# Adafruit_VL53L4CD.net
KiCad netlist of a schematic drawn in EAGLE
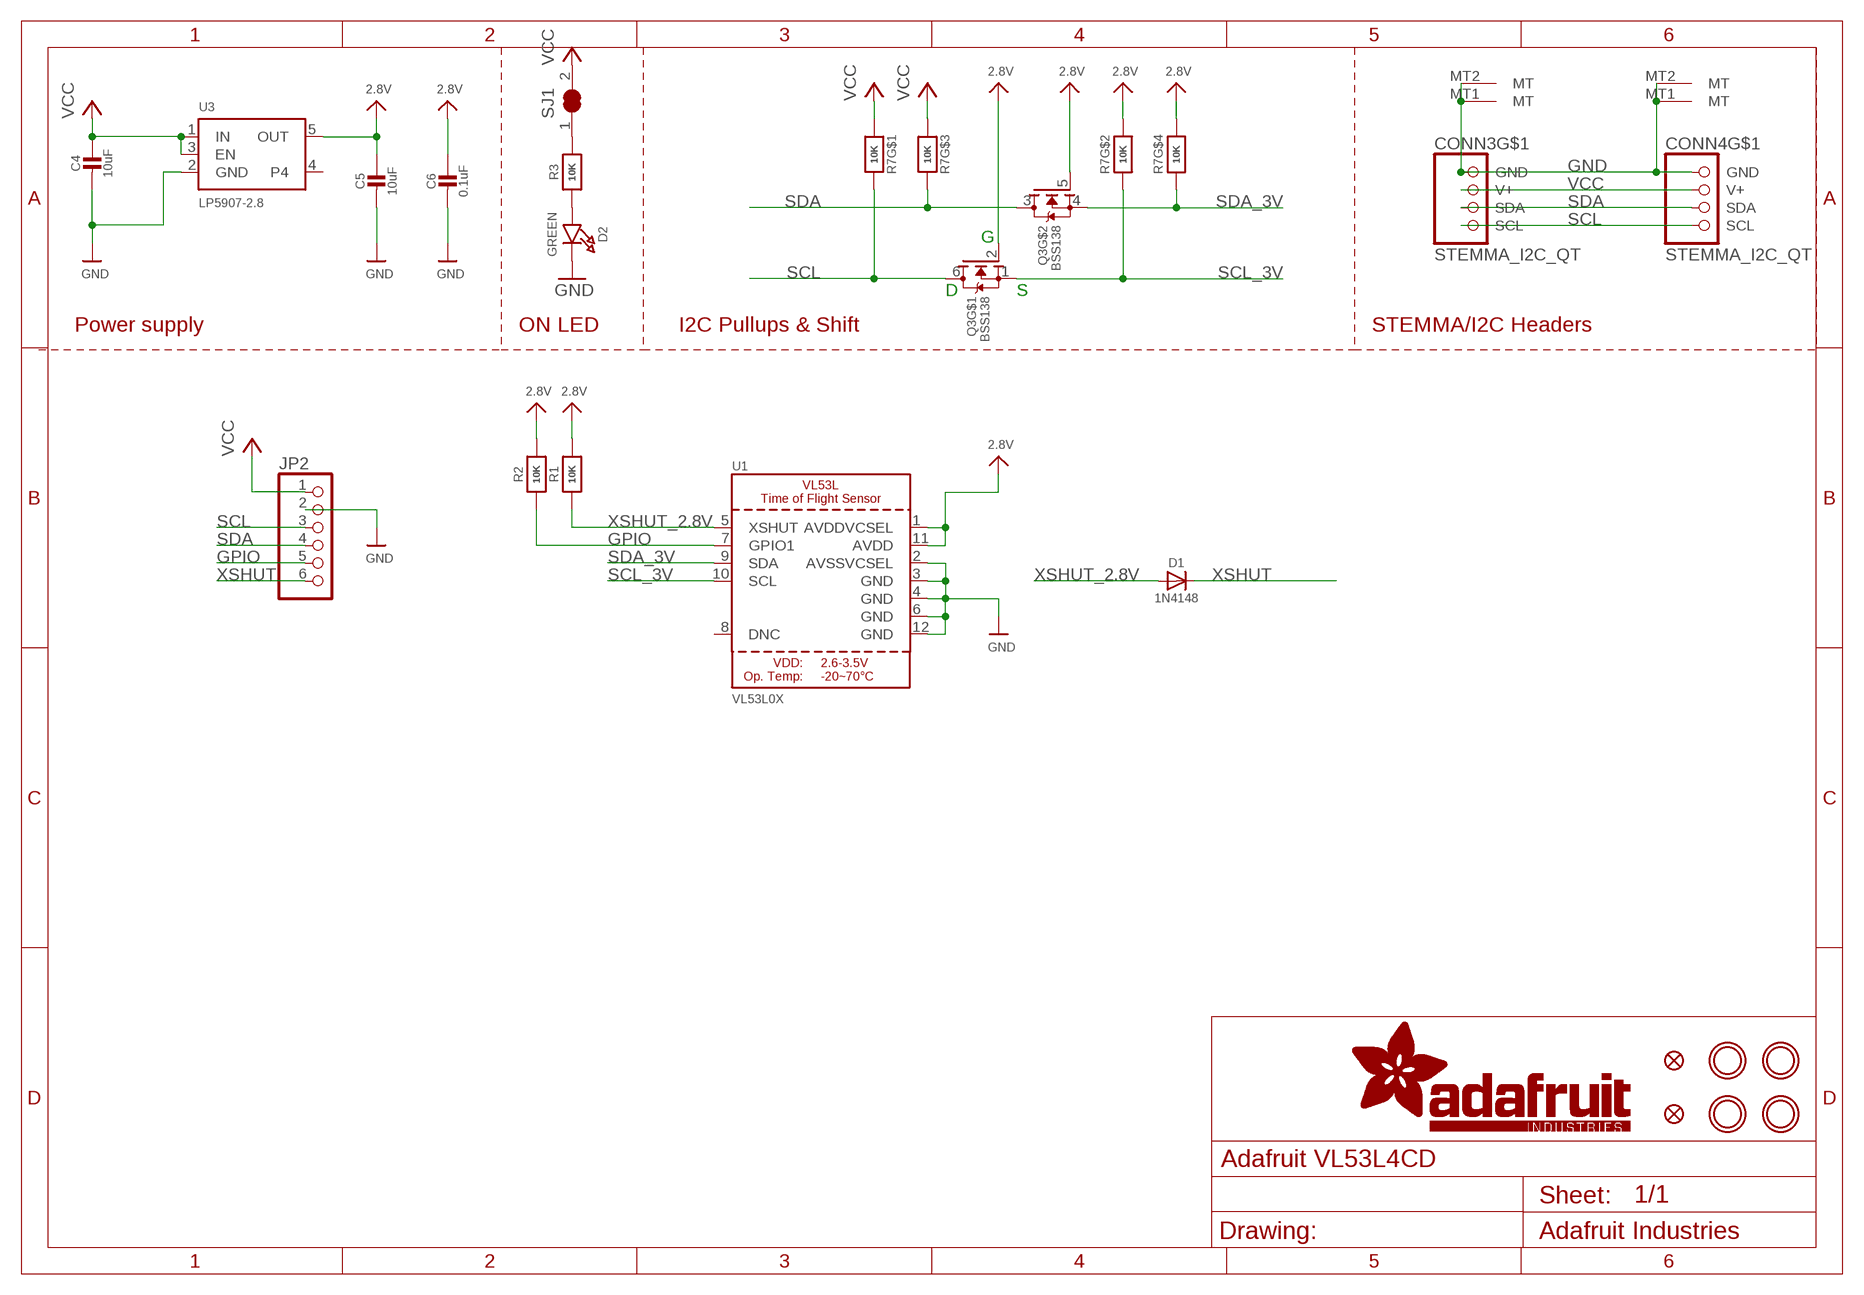
[diagram p0: schematic, sheet 1]

(export (version "E")
  (design (tool "Eeschema 10.0.6"))
  (components
    (comp (ref "C4")
      (value "10uF")
      (footprint "eagle-import:0805-NO")
      (libsource (lib "eagle-import") (part "CAP_CERAMIC0805-NOOUTLINE"))
    )
    (comp (ref "C5")
      (value "10uF")
      (footprint "eagle-import:0805-NO")
      (libsource (lib "eagle-import") (part "CAP_CERAMIC0805-NOOUTLINE"))
    )
    (comp (ref "C6")
      (value "0.1uF")
      (footprint "eagle-import:0603-NO")
      (libsource (lib "eagle-import") (part "CAP_CERAMIC0603_NO"))
    )
    (comp (ref "CONN3")
      (value "STEMMA_I2C_QT")
      (footprint "eagle-import:JST_SH4")
      (libsource (lib "eagle-import") (part "STEMMA_I2C_QT"))
    )
    (comp (ref "CONN4")
      (value "STEMMA_I2C_QT")
      (footprint "eagle-import:JST_SH4")
      (libsource (lib "eagle-import") (part "STEMMA_I2C_QT"))
    )
    (comp (ref "D1")
      (value "1N4148")
      (footprint "eagle-import:SOD-323")
      (libsource (lib "eagle-import") (part "DIODESOD-323"))
    )
    (comp (ref "D2")
      (value "GREEN")
      (footprint "eagle-import:CHIPLED_0603_NOOUTLINE")
      (libsource (lib "eagle-import") (part "LED0603_NOOUTLINE"))
    )
    (comp (ref "FID1")
      (value "FIDUCIAL_1MM")
      (footprint "eagle-import:FIDUCIAL_1MM")
      (libsource (lib "eagle-import") (part "FIDUCIAL_1MM"))
    )
    (comp (ref "FID4")
      (value "FIDUCIAL_1MM")
      (footprint "eagle-import:FIDUCIAL_1MM")
      (libsource (lib "eagle-import") (part "FIDUCIAL_1MM"))
    )
    (comp (ref "JP2")
      (value "HEADER-1X670MIL")
      (footprint "eagle-import:1X06_ROUND_70")
      (libsource (lib "eagle-import") (part "HEADER-1X670MIL"))
    )
    (comp (ref "Q3")
      (value "BSS138")
      (footprint "eagle-import:SOT363")
      (libsource (lib "eagle-import") (part "MOSFET-N_DUAL"))
    )
    (comp (ref "R1")
      (value "10K")
      (footprint "eagle-import:0603-NO")
      (libsource (lib "eagle-import") (part "RESISTOR_0603_NOOUT"))
    )
    (comp (ref "R2")
      (value "10K")
      (footprint "eagle-import:0603-NO")
      (libsource (lib "eagle-import") (part "RESISTOR_0603_NOOUT"))
    )
    (comp (ref "R3")
      (value "10K")
      (footprint "eagle-import:0603-NO")
      (libsource (lib "eagle-import") (part "RESISTOR_0603_NOOUT"))
    )
    (comp (ref "R7")
      (value "10K")
      (footprint "eagle-import:RESPACK_4X0603")
      (libsource (lib "eagle-import") (part "RESISTOR_4PACK"))
    )
    (comp (ref "SJ1")
      (value "SOLDERJUMPER_CLOSED")
      (footprint "eagle-import:SOLDERJUMPER_CLOSEDWIRE")
      (libsource (lib "eagle-import") (part "SOLDERJUMPER_CLOSED"))
    )
    (comp (ref "U$30")
      (value "MOUNTINGHOLE2.5")
      (footprint "eagle-import:MOUNTINGHOLE_2.5_PLATED")
      (libsource (lib "eagle-import") (part "MOUNTINGHOLE2.5"))
    )
    (comp (ref "U$31")
      (value "MOUNTINGHOLE2.5")
      (footprint "eagle-import:MOUNTINGHOLE_2.5_PLATED")
      (libsource (lib "eagle-import") (part "MOUNTINGHOLE2.5"))
    )
    (comp (ref "U$33")
      (value "MOUNTINGHOLE2.5")
      (footprint "eagle-import:MOUNTINGHOLE_2.5_PLATED")
      (libsource (lib "eagle-import") (part "MOUNTINGHOLE2.5"))
    )
    (comp (ref "U$34")
      (value "MOUNTINGHOLE2.5")
      (footprint "eagle-import:MOUNTINGHOLE_2.5_PLATED")
      (libsource (lib "eagle-import") (part "MOUNTINGHOLE2.5"))
    )
    (comp (ref "U1")
      (value "VL53L0X")
      (footprint "eagle-import:LGA12_ST")
      (libsource (lib "eagle-import") (part "VL53L0X"))
    )
    (comp (ref "U3")
      (value "LP5907-2.8")
      (footprint "eagle-import:SOT23-5")
      (libsource (lib "eagle-import") (part "VREG_SOT23-5"))
    )
  )
  (nets
    (net (code "1") (name "/GPIO") (class "Default")
      (node (ref "JP2") (pin "5") (pinfunction "5_5") (pintype "passive"))
      (node (ref "R2") (pin "1") (pinfunction "1_1") (pintype "passive"))
      (node (ref "U1") (pin "7") (pinfunction "GPIO1_7") (pintype "output"))
    )
    (net (code "2") (name "/SCL") (class "Default")
      (node (ref "CONN3") (pin "4") (pinfunction "SCL_4") (pintype "passive"))
      (node (ref "CONN4") (pin "4") (pinfunction "SCL_4") (pintype "passive"))
      (node (ref "JP2") (pin "3") (pinfunction "3_3") (pintype "passive"))
      (node (ref "Q3") (pin "6") (pinfunction "D_6") (pintype "bidirectional"))
      (node (ref "R7") (pin "8") (pinfunction "2_8") (pintype "passive"))
    )
    (net (code "3") (name "/SCL_3V") (class "Default")
      (node (ref "Q3") (pin "1") (pinfunction "S_1") (pintype "bidirectional"))
      (node (ref "R7") (pin "7") (pinfunction "2_7") (pintype "passive"))
      (node (ref "U1") (pin "10") (pinfunction "SCL_10") (pintype "open_collector"))
    )
    (net (code "4") (name "/SDA") (class "Default")
      (node (ref "CONN3") (pin "3") (pinfunction "SDA_3") (pintype "passive"))
      (node (ref "CONN4") (pin "3") (pinfunction "SDA_3") (pintype "passive"))
      (node (ref "JP2") (pin "4") (pinfunction "4_4") (pintype "passive"))
      (node (ref "Q3") (pin "3") (pinfunction "D_3") (pintype "bidirectional"))
      (node (ref "R7") (pin "6") (pinfunction "2_6") (pintype "passive"))
    )
    (net (code "5") (name "/SDA_3V") (class "Default")
      (node (ref "Q3") (pin "4") (pinfunction "S_4") (pintype "bidirectional"))
      (node (ref "R7") (pin "5") (pinfunction "2_5") (pintype "passive"))
      (node (ref "U1") (pin "9") (pinfunction "SDA_9") (pintype "open_collector"))
    )
    (net (code "6") (name "/XSHUT") (class "Default")
      (node (ref "D1") (pin "C") (pinfunction "C_C") (pintype "passive"))
      (node (ref "JP2") (pin "6") (pinfunction "6_6") (pintype "passive"))
    )
    (net (code "7") (name "/XSHUT_2.8V") (class "Default")
      (node (ref "D1") (pin "A") (pinfunction "A_A") (pintype "passive"))
      (node (ref "R1") (pin "1") (pinfunction "1_1") (pintype "passive"))
      (node (ref "U1") (pin "5") (pinfunction "XSHUT_5") (pintype "input"))
    )
    (net (code "8") (name "2.8V") (class "Default")
      (node (ref "C5") (pin "1") (pinfunction "1_1") (pintype "passive"))
      (node (ref "C6") (pin "1") (pinfunction "1_1") (pintype "passive"))
      (node (ref "Q3") (pin "2") (pinfunction "G_2") (pintype "bidirectional"))
      (node (ref "Q3") (pin "5") (pinfunction "G_5") (pintype "bidirectional"))
      (node (ref "R1") (pin "2") (pinfunction "2_2") (pintype "passive"))
      (node (ref "R2") (pin "2") (pinfunction "2_2") (pintype "passive"))
      (node (ref "R7") (pin "2") (pinfunction "1_2") (pintype "passive"))
      (node (ref "R7") (pin "4") (pinfunction "1_4") (pintype "passive"))
      (node (ref "U1") (pin "1") (pinfunction "AVDDVCSEL_1") (pintype "power_in"))
      (node (ref "U1") (pin "11") (pinfunction "AVDD_11") (pintype "power_in"))
      (node (ref "U3") (pin "5") (pinfunction "OUT_5") (pintype "power_in"))
    )
    (net (code "9") (name "GND") (class "Default")
      (node (ref "C4") (pin "2") (pinfunction "2_2") (pintype "passive"))
      (node (ref "C5") (pin "2") (pinfunction "2_2") (pintype "passive"))
      (node (ref "C6") (pin "2") (pinfunction "2_2") (pintype "passive"))
      (node (ref "CONN3") (pin "1") (pinfunction "GND_1") (pintype "passive"))
      (node (ref "CONN3") (pin "MT1") (pinfunction "MT_MT1") (pintype "bidirectional"))
      (node (ref "CONN3") (pin "MT2") (pinfunction "MT_MT2") (pintype "bidirectional"))
      (node (ref "CONN4") (pin "1") (pinfunction "GND_1") (pintype "passive"))
      (node (ref "CONN4") (pin "MT1") (pinfunction "MT_MT1") (pintype "bidirectional"))
      (node (ref "CONN4") (pin "MT2") (pinfunction "MT_MT2") (pintype "bidirectional"))
      (node (ref "D2") (pin "C") (pinfunction "C_C") (pintype "passive"))
      (node (ref "JP2") (pin "2") (pinfunction "2_2") (pintype "passive"))
      (node (ref "U1") (pin "12") (pinfunction "GND_12") (pintype "power_in"))
      (node (ref "U1") (pin "2") (pinfunction "AVSSVCSEL_2") (pintype "power_in"))
      (node (ref "U1") (pin "3") (pinfunction "GND_3") (pintype "power_in"))
      (node (ref "U1") (pin "4") (pinfunction "GND_4") (pintype "power_in"))
      (node (ref "U1") (pin "6") (pinfunction "GND_6") (pintype "power_in"))
      (node (ref "U3") (pin "2") (pinfunction "GND_2") (pintype "power_in"))
    )
    (net (code "10") (name "Net-(D2-PadA)") (class "Default")
      (node (ref "D2") (pin "A") (pinfunction "A_A") (pintype "passive"))
      (node (ref "R3") (pin "1") (pinfunction "1_1") (pintype "passive"))
    )
    (net (code "11") (name "Net-(R3-Pad2)") (class "Default")
      (node (ref "R3") (pin "2") (pinfunction "2_2") (pintype "passive"))
      (node (ref "SJ1") (pin "1") (pinfunction "1_1") (pintype "passive"))
    )
    (net (code "12") (name "VCC") (class "Default")
      (node (ref "C4") (pin "1") (pinfunction "1_1") (pintype "passive"))
      (node (ref "CONN3") (pin "2") (pinfunction "V+_2") (pintype "passive"))
      (node (ref "CONN4") (pin "2") (pinfunction "V+_2") (pintype "passive"))
      (node (ref "JP2") (pin "1") (pinfunction "1_1") (pintype "passive"))
      (node (ref "R7") (pin "1") (pinfunction "1_1") (pintype "passive"))
      (node (ref "R7") (pin "3") (pinfunction "1_3") (pintype "passive"))
      (node (ref "SJ1") (pin "2") (pinfunction "2_2") (pintype "passive"))
      (node (ref "U3") (pin "1") (pinfunction "IN_1") (pintype "power_in"))
      (node (ref "U3") (pin "3") (pinfunction "EN_3") (pintype "input"))
    )
    (net (code "13") (name "unconnected-(U1-DNC-Pad8)") (class "Default")
      (node (ref "U1") (pin "8") (pinfunction "DNC_8") (pintype "no_connect"))
    )
    (net (code "14") (name "unconnected-(U3-P4-Pad4)") (class "Default")
      (node (ref "U3") (pin "4") (pinfunction "P4_4") (pintype "bidirectional"))
    )
  )
)
